# Sheet_1_2026-05-05.net
KiCad netlist of a schematic drawn in Altium Designer
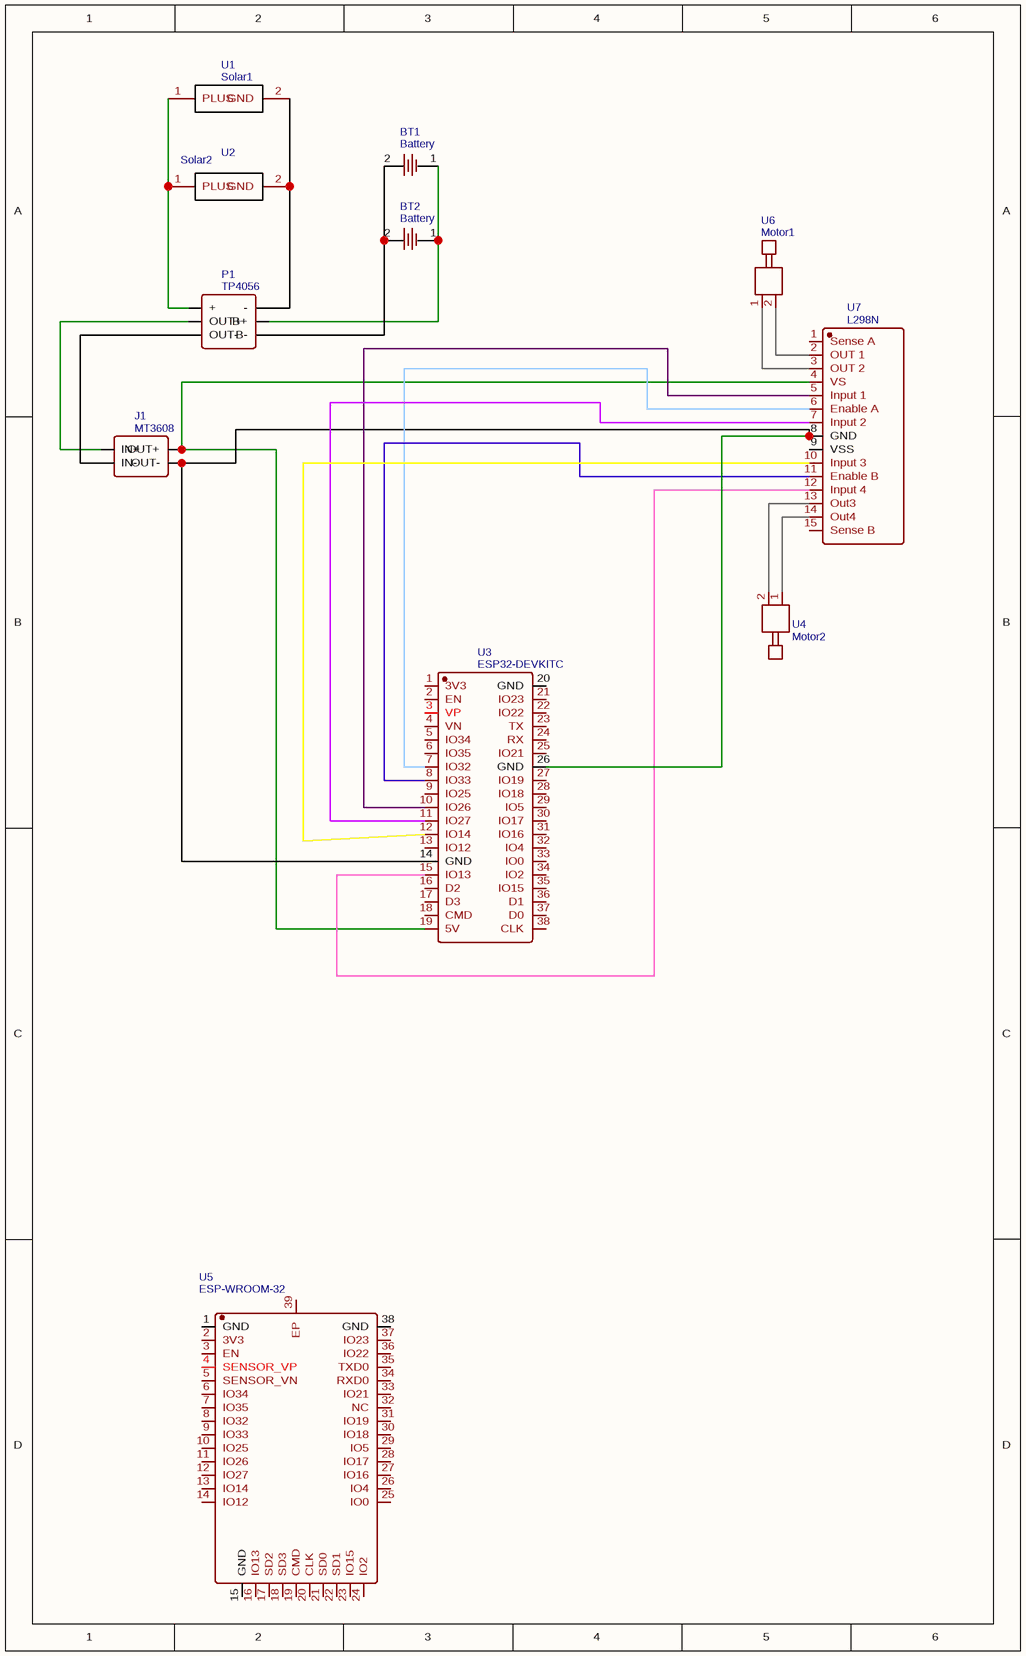
[diagram p0: Sheet_1_2026-05-05.schdoc]

(export (version "E")
  (design (tool "Eeschema 10.0.6"))
  (components
    (comp (ref "BT1")
      (value "Battery")
      (fields
        (field (name "MANUFACTURER") "MYOUNG(美阳)")
        (field (name "MANUFACTURER PART") "BH-18650-B1BA002")
        (field (name "CONTRIBUTOR") "lcsc")
      )
      (libsource (lib "altium-import") (part "root_0_Battery_"))
    )
    (comp (ref "BT2")
      (value "Battery")
      (fields
        (field (name "MANUFACTURER") "MYOUNG(美阳)")
        (field (name "MANUFACTURER PART") "BH-18650-B1BA002")
        (field (name "CONTRIBUTOR") "lcsc")
      )
      (libsource (lib "altium-import") (part "root_0_Battery_"))
    )
    (comp (ref "J1")
      (value "MT3608")
      (fields (field (name "CONTRIBUTOR") "LCEDA_Lib"))
      (libsource (lib "altium-import") (part "root_0_MT3608_"))
    )
    (comp (ref "P1")
      (value "TP4056")
      (fields (field (name "MANUFACTURER") "BOOMELE") (field (name "MANUFACTURER PART") "2X3 2.54mm IDC Box"))
      (libsource (lib "altium-import") (part "root_0_TP4056_"))
    )
    (comp (ref "U1")
      (value "Solar1")
      (fields (field (name "CONTRIBUTOR") "klaslofstedt"))
      (libsource (lib "altium-import") (part "root_0_Solar1_"))
    )
    (comp (ref "U2")
      (value "Solar2")
      (fields (field (name "CONTRIBUTOR") "klaslofstedt"))
      (libsource (lib "altium-import") (part "root_0_Solar2_"))
    )
    (comp (ref "U3")
      (value "ESP32-DEVKITC")
      (fields
        (field (name "MANUFACTURER") "ESPRESSIF(乐鑫)")
        (field (name "MANUFACTURER PART") "ESP32-DevKitC")
        (field (name "CONTRIBUTOR") "lcsc")
      )
      (libsource (lib "altium-import") (part "root_0_ESP32-DEVKITC_"))
    )
    (comp (ref "U4")
      (value "Motor2")
      (fields
        (field (name "MANUFACTURER") "LEADER(立得)")
        (field (name "MANUFACTURER PART") "LCM04084521-B1")
        (field (name "CONTRIBUTOR") "lcsc")
      )
      (libsource (lib "altium-import") (part "root_2_Motor2_"))
    )
    (comp (ref "U5")
      (value "ESP-WROOM-32")
      (fields
        (field (name "MANUFACTURER") "ESPRESSIF(乐鑫)")
        (field (name "MANUFACTURER PART") "ESP32-WROOM-32")
      )
      (libsource (lib "altium-import") (part "root_0_ESP-WROOM-32_"))
    )
    (comp (ref "U6")
      (value "Motor1")
      (fields
        (field (name "MANUFACTURER") "LEADER(立得)")
        (field (name "MANUFACTURER PART") "LCM04084521-B1")
        (field (name "CONTRIBUTOR") "lcsc")
      )
      (libsource (lib "altium-import") (part "root_0_Motor1_"))
    )
    (comp (ref "U7")
      (value "L298N")
      (fields (field (name "MANUFACTURER") "HGSEMI(华冠)") (field (name "CONTRIBUTOR") "LCSC"))
      (libsource (lib "altium-import") (part "root_0_L298N_"))
    )
  )
  (nets
    (net (code "1") (name "Net-(J1-IN+)") (class "Default")
      (node (ref "J1") (pin "1") (pinfunction "IN+_1") (pintype "passive"))
      (node (ref "P1") (pin "3") (pinfunction "OUT+_3") (pintype "passive"))
    )
    (net (code "2") (name "Net-(J1-IN-)") (class "Default")
      (node (ref "J1") (pin "3") (pinfunction "IN-_3") (pintype "passive"))
      (node (ref "P1") (pin "5") (pinfunction "OUT-_5") (pintype "passive"))
    )
    (net (code "3") (name "Net-(J1-OUT+)") (class "Default")
      (node (ref "J1") (pin "2") (pinfunction "OUT+_2") (pintype "passive"))
      (node (ref "U3") (pin "19") (pinfunction "5V_19") (pintype "passive"))
      (node (ref "U7") (pin "4") (pinfunction "VS_4") (pintype "passive"))
    )
    (net (code "4") (name "Net-(J1-OUT-)") (class "Default")
      (node (ref "J1") (pin "4") (pinfunction "OUT-_4") (pintype "passive"))
      (node (ref "U3") (pin "14") (pinfunction "GND_14") (pintype "passive"))
      (node (ref "U3") (pin "26") (pinfunction "GND_26") (pintype "passive"))
      (node (ref "U7") (pin "8") (pinfunction "GND_8") (pintype "passive"))
    )
    (net (code "5") (name "Net-(P1-+)") (class "Default")
      (node (ref "P1") (pin "1") (pinfunction "+_1") (pintype "passive"))
      (node (ref "U1") (pin "1") (pinfunction "PLUS_1") (pintype "passive"))
      (node (ref "U2") (pin "1") (pinfunction "PLUS_1") (pintype "passive"))
    )
    (net (code "6") (name "Net-(P1--)") (class "Default")
      (node (ref "P1") (pin "2") (pinfunction "-_2") (pintype "passive"))
      (node (ref "U1") (pin "2") (pinfunction "GND_2") (pintype "passive"))
      (node (ref "U2") (pin "2") (pinfunction "GND_2") (pintype "passive"))
    )
    (net (code "7") (name "Net-(P1-B+)") (class "Default")
      (node (ref "BT1") (pin "1") (pinfunction "1_1") (pintype "passive"))
      (node (ref "BT2") (pin "1") (pinfunction "1_1") (pintype "passive"))
      (node (ref "P1") (pin "4") (pinfunction "B+_4") (pintype "passive"))
    )
    (net (code "8") (name "Net-(P1-B-)") (class "Default")
      (node (ref "BT1") (pin "2") (pinfunction "2_2") (pintype "passive"))
      (node (ref "BT2") (pin "2") (pinfunction "2_2") (pintype "passive"))
      (node (ref "P1") (pin "6") (pinfunction "B-_6") (pintype "passive"))
    )
    (net (code "9") (name "Net-(U3-IO13)") (class "Default")
      (node (ref "U3") (pin "15") (pinfunction "IO13_15") (pintype "passive"))
      (node (ref "U7") (pin "12") (pinfunction "Input_4_12") (pintype "passive"))
    )
    (net (code "10") (name "Net-(U3-IO14)") (class "Default")
      (node (ref "U3") (pin "12") (pinfunction "IO14_12") (pintype "passive"))
      (node (ref "U7") (pin "10") (pinfunction "Input_3_10") (pintype "passive"))
    )
    (net (code "11") (name "Net-(U3-IO26)") (class "Default")
      (node (ref "U3") (pin "10") (pinfunction "IO26_10") (pintype "passive"))
      (node (ref "U7") (pin "5") (pinfunction "Input_1_5") (pintype "passive"))
    )
    (net (code "12") (name "Net-(U3-IO27)") (class "Default")
      (node (ref "U3") (pin "11") (pinfunction "IO27_11") (pintype "passive"))
      (node (ref "U7") (pin "7") (pinfunction "Input_2_7") (pintype "passive"))
    )
    (net (code "13") (name "Net-(U3-IO32)") (class "Default")
      (node (ref "U3") (pin "7") (pinfunction "IO32_7") (pintype "passive"))
      (node (ref "U7") (pin "6") (pinfunction "Enable_A_6") (pintype "passive"))
    )
    (net (code "14") (name "Net-(U3-IO33)") (class "Default")
      (node (ref "U3") (pin "8") (pinfunction "IO33_8") (pintype "passive"))
      (node (ref "U7") (pin "11") (pinfunction "Enable_B_11") (pintype "passive"))
    )
    (net (code "15") (name "Net-(U7-OUT_1)") (class "Default")
      (node (ref "U6") (pin "2") (pinfunction "2_2") (pintype "passive"))
      (node (ref "U7") (pin "2") (pinfunction "OUT_1_2") (pintype "passive"))
    )
    (net (code "16") (name "Net-(U7-OUT_2)") (class "Default")
      (node (ref "U6") (pin "1") (pinfunction "1_1") (pintype "passive"))
      (node (ref "U7") (pin "3") (pinfunction "OUT_2_3") (pintype "passive"))
    )
    (net (code "17") (name "Net-(U7-Out3)") (class "Default")
      (node (ref "U4") (pin "2") (pinfunction "2_2") (pintype "passive"))
      (node (ref "U7") (pin "13") (pinfunction "Out3_13") (pintype "passive"))
    )
    (net (code "18") (name "Net-(U7-Out4)") (class "Default")
      (node (ref "U4") (pin "1") (pinfunction "1_1") (pintype "passive"))
      (node (ref "U7") (pin "14") (pinfunction "Out4_14") (pintype "passive"))
    )
    (net (code "19") (name "unconnected-(U3-3V3-Pad1)") (class "Default")
      (node (ref "U3") (pin "1") (pinfunction "3V3_1") (pintype "passive"))
    )
    (net (code "20") (name "unconnected-(U3-CLK-Pad38)") (class "Default")
      (node (ref "U3") (pin "38") (pinfunction "CLK_38") (pintype "passive"))
    )
    (net (code "21") (name "unconnected-(U3-CMD-Pad18)") (class "Default")
      (node (ref "U3") (pin "18") (pinfunction "CMD_18") (pintype "passive"))
    )
    (net (code "22") (name "unconnected-(U3-D0-Pad37)") (class "Default")
      (node (ref "U3") (pin "37") (pinfunction "D0_37") (pintype "passive"))
    )
    (net (code "23") (name "unconnected-(U3-D1-Pad36)") (class "Default")
      (node (ref "U3") (pin "36") (pinfunction "D1_36") (pintype "passive"))
    )
    (net (code "24") (name "unconnected-(U3-D2-Pad16)") (class "Default")
      (node (ref "U3") (pin "16") (pinfunction "D2_16") (pintype "passive"))
    )
    (net (code "25") (name "unconnected-(U3-D3-Pad17)") (class "Default")
      (node (ref "U3") (pin "17") (pinfunction "D3_17") (pintype "passive"))
    )
    (net (code "26") (name "unconnected-(U3-EN-Pad2)") (class "Default")
      (node (ref "U3") (pin "2") (pinfunction "EN_2") (pintype "passive"))
    )
    (net (code "27") (name "unconnected-(U3-GND-Pad20)") (class "Default")
      (node (ref "U3") (pin "20") (pinfunction "GND_20") (pintype "passive"))
    )
    (net (code "28") (name "unconnected-(U3-IO0-Pad33)") (class "Default")
      (node (ref "U3") (pin "33") (pinfunction "IO0_33") (pintype "passive"))
    )
    (net (code "29") (name "unconnected-(U3-IO2-Pad34)") (class "Default")
      (node (ref "U3") (pin "34") (pinfunction "IO2_34") (pintype "passive"))
    )
    (net (code "30") (name "unconnected-(U3-IO4-Pad32)") (class "Default")
      (node (ref "U3") (pin "32") (pinfunction "IO4_32") (pintype "passive"))
    )
    (net (code "31") (name "unconnected-(U3-IO5-Pad29)") (class "Default")
      (node (ref "U3") (pin "29") (pinfunction "IO5_29") (pintype "passive"))
    )
    (net (code "32") (name "unconnected-(U3-IO12-Pad13)") (class "Default")
      (node (ref "U3") (pin "13") (pinfunction "IO12_13") (pintype "passive"))
    )
    (net (code "33") (name "unconnected-(U3-IO15-Pad35)") (class "Default")
      (node (ref "U3") (pin "35") (pinfunction "IO15_35") (pintype "passive"))
    )
    (net (code "34") (name "unconnected-(U3-IO16-Pad31)") (class "Default")
      (node (ref "U3") (pin "31") (pinfunction "IO16_31") (pintype "passive"))
    )
    (net (code "35") (name "unconnected-(U3-IO17-Pad30)") (class "Default")
      (node (ref "U3") (pin "30") (pinfunction "IO17_30") (pintype "passive"))
    )
    (net (code "36") (name "unconnected-(U3-IO18-Pad28)") (class "Default")
      (node (ref "U3") (pin "28") (pinfunction "IO18_28") (pintype "passive"))
    )
    (net (code "37") (name "unconnected-(U3-IO19-Pad27)") (class "Default")
      (node (ref "U3") (pin "27") (pinfunction "IO19_27") (pintype "passive"))
    )
    (net (code "38") (name "unconnected-(U3-IO21-Pad25)") (class "Default")
      (node (ref "U3") (pin "25") (pinfunction "IO21_25") (pintype "passive"))
    )
    (net (code "39") (name "unconnected-(U3-IO22-Pad22)") (class "Default")
      (node (ref "U3") (pin "22") (pinfunction "IO22_22") (pintype "passive"))
    )
    (net (code "40") (name "unconnected-(U3-IO23-Pad21)") (class "Default")
      (node (ref "U3") (pin "21") (pinfunction "IO23_21") (pintype "passive"))
    )
    (net (code "41") (name "unconnected-(U3-IO25-Pad9)") (class "Default")
      (node (ref "U3") (pin "9") (pinfunction "IO25_9") (pintype "passive"))
    )
    (net (code "42") (name "unconnected-(U3-IO34-Pad5)") (class "Default")
      (node (ref "U3") (pin "5") (pinfunction "IO34_5") (pintype "passive"))
    )
    (net (code "43") (name "unconnected-(U3-IO35-Pad6)") (class "Default")
      (node (ref "U3") (pin "6") (pinfunction "IO35_6") (pintype "passive"))
    )
    (net (code "44") (name "unconnected-(U3-RX-Pad24)") (class "Default")
      (node (ref "U3") (pin "24") (pinfunction "RX_24") (pintype "passive"))
    )
    (net (code "45") (name "unconnected-(U3-TX-Pad23)") (class "Default")
      (node (ref "U3") (pin "23") (pinfunction "TX_23") (pintype "passive"))
    )
    (net (code "46") (name "unconnected-(U3-VN-Pad4)") (class "Default")
      (node (ref "U3") (pin "4") (pinfunction "VN_4") (pintype "passive"))
    )
    (net (code "47") (name "unconnected-(U3-VP-Pad3)") (class "Default")
      (node (ref "U3") (pin "3") (pinfunction "VP_3") (pintype "passive"))
    )
    (net (code "48") (name "unconnected-(U5-3V3-Pad2)") (class "Default")
      (node (ref "U5") (pin "2") (pinfunction "3V3_2") (pintype "passive"))
    )
    (net (code "49") (name "unconnected-(U5-CLK-Pad20)") (class "Default")
      (node (ref "U5") (pin "20") (pinfunction "CLK_20") (pintype "passive"))
    )
    (net (code "50") (name "unconnected-(U5-CMD-Pad19)") (class "Default")
      (node (ref "U5") (pin "19") (pinfunction "CMD_19") (pintype "passive"))
    )
    (net (code "51") (name "unconnected-(U5-EN-Pad3)") (class "Default")
      (node (ref "U5") (pin "3") (pinfunction "EN_3") (pintype "passive"))
    )
    (net (code "52") (name "unconnected-(U5-EP-Pad39)") (class "Default")
      (node (ref "U5") (pin "39") (pinfunction "EP_39") (pintype "passive"))
    )
    (net (code "53") (name "unconnected-(U5-GND-Pad1)") (class "Default")
      (node (ref "U5") (pin "1") (pinfunction "GND_1") (pintype "passive"))
    )
    (net (code "54") (name "unconnected-(U5-GND-Pad15)") (class "Default")
      (node (ref "U5") (pin "15") (pinfunction "GND_15") (pintype "passive"))
    )
    (net (code "55") (name "unconnected-(U5-GND-Pad38)") (class "Default")
      (node (ref "U5") (pin "38") (pinfunction "GND_38") (pintype "passive"))
    )
    (net (code "56") (name "unconnected-(U5-IO0-Pad25)") (class "Default")
      (node (ref "U5") (pin "25") (pinfunction "IO0_25") (pintype "passive"))
    )
    (net (code "57") (name "unconnected-(U5-IO2-Pad24)") (class "Default")
      (node (ref "U5") (pin "24") (pinfunction "IO2_24") (pintype "passive"))
    )
    (net (code "58") (name "unconnected-(U5-IO4-Pad26)") (class "Default")
      (node (ref "U5") (pin "26") (pinfunction "IO4_26") (pintype "passive"))
    )
    (net (code "59") (name "unconnected-(U5-IO5-Pad29)") (class "Default")
      (node (ref "U5") (pin "29") (pinfunction "IO5_29") (pintype "passive"))
    )
    (net (code "60") (name "unconnected-(U5-IO12-Pad14)") (class "Default")
      (node (ref "U5") (pin "14") (pinfunction "IO12_14") (pintype "passive"))
    )
    (net (code "61") (name "unconnected-(U5-IO13-Pad16)") (class "Default")
      (node (ref "U5") (pin "16") (pinfunction "IO13_16") (pintype "passive"))
    )
    (net (code "62") (name "unconnected-(U5-IO14-Pad13)") (class "Default")
      (node (ref "U5") (pin "13") (pinfunction "IO14_13") (pintype "passive"))
    )
    (net (code "63") (name "unconnected-(U5-IO15-Pad23)") (class "Default")
      (node (ref "U5") (pin "23") (pinfunction "IO15_23") (pintype "passive"))
    )
    (net (code "64") (name "unconnected-(U5-IO16-Pad27)") (class "Default")
      (node (ref "U5") (pin "27") (pinfunction "IO16_27") (pintype "passive"))
    )
    (net (code "65") (name "unconnected-(U5-IO17-Pad28)") (class "Default")
      (node (ref "U5") (pin "28") (pinfunction "IO17_28") (pintype "passive"))
    )
    (net (code "66") (name "unconnected-(U5-IO18-Pad30)") (class "Default")
      (node (ref "U5") (pin "30") (pinfunction "IO18_30") (pintype "passive"))
    )
    (net (code "67") (name "unconnected-(U5-IO19-Pad31)") (class "Default")
      (node (ref "U5") (pin "31") (pinfunction "IO19_31") (pintype "passive"))
    )
    (net (code "68") (name "unconnected-(U5-IO21-Pad33)") (class "Default")
      (node (ref "U5") (pin "33") (pinfunction "IO21_33") (pintype "passive"))
    )
    (net (code "69") (name "unconnected-(U5-IO22-Pad36)") (class "Default")
      (node (ref "U5") (pin "36") (pinfunction "IO22_36") (pintype "passive"))
    )
    (net (code "70") (name "unconnected-(U5-IO23-Pad37)") (class "Default")
      (node (ref "U5") (pin "37") (pinfunction "IO23_37") (pintype "passive"))
    )
    (net (code "71") (name "unconnected-(U5-IO25-Pad10)") (class "Default")
      (node (ref "U5") (pin "10") (pinfunction "IO25_10") (pintype "passive"))
    )
    (net (code "72") (name "unconnected-(U5-IO26-Pad11)") (class "Default")
      (node (ref "U5") (pin "11") (pinfunction "IO26_11") (pintype "passive"))
    )
    (net (code "73") (name "unconnected-(U5-IO27-Pad12)") (class "Default")
      (node (ref "U5") (pin "12") (pinfunction "IO27_12") (pintype "passive"))
    )
    (net (code "74") (name "unconnected-(U5-IO32-Pad8)") (class "Default")
      (node (ref "U5") (pin "8") (pinfunction "IO32_8") (pintype "passive"))
    )
    (net (code "75") (name "unconnected-(U5-IO33-Pad9)") (class "Default")
      (node (ref "U5") (pin "9") (pinfunction "IO33_9") (pintype "passive"))
    )
    (net (code "76") (name "unconnected-(U5-IO34-Pad6)") (class "Default")
      (node (ref "U5") (pin "6") (pinfunction "IO34_6") (pintype "passive"))
    )
    (net (code "77") (name "unconnected-(U5-IO35-Pad7)") (class "Default")
      (node (ref "U5") (pin "7") (pinfunction "IO35_7") (pintype "passive"))
    )
    (net (code "78") (name "unconnected-(U5-NC-Pad32)") (class "Default")
      (node (ref "U5") (pin "32") (pinfunction "NC_32") (pintype "passive"))
    )
    (net (code "79") (name "unconnected-(U5-RXD0-Pad34)") (class "Default")
      (node (ref "U5") (pin "34") (pinfunction "RXD0_34") (pintype "passive"))
    )
    (net (code "80") (name "unconnected-(U5-SD0-Pad21)") (class "Default")
      (node (ref "U5") (pin "21") (pinfunction "SD0_21") (pintype "passive"))
    )
    (net (code "81") (name "unconnected-(U5-SD1-Pad22)") (class "Default")
      (node (ref "U5") (pin "22") (pinfunction "SD1_22") (pintype "passive"))
    )
    (net (code "82") (name "unconnected-(U5-SD2-Pad17)") (class "Default")
      (node (ref "U5") (pin "17") (pinfunction "SD2_17") (pintype "passive"))
    )
    (net (code "83") (name "unconnected-(U5-SD3-Pad18)") (class "Default")
      (node (ref "U5") (pin "18") (pinfunction "SD3_18") (pintype "passive"))
    )
    (net (code "84") (name "unconnected-(U5-SENSOR_VN-Pad5)") (class "Default")
      (node (ref "U5") (pin "5") (pinfunction "SENSOR_VN_5") (pintype "passive"))
    )
    (net (code "85") (name "unconnected-(U5-SENSOR_VP-Pad4)") (class "Default")
      (node (ref "U5") (pin "4") (pinfunction "SENSOR_VP_4") (pintype "passive"))
    )
    (net (code "86") (name "unconnected-(U5-TXD0-Pad35)") (class "Default")
      (node (ref "U5") (pin "35") (pinfunction "TXD0_35") (pintype "passive"))
    )
    (net (code "87") (name "unconnected-(U7-Sense_A-Pad1)") (class "Default")
      (node (ref "U7") (pin "1") (pinfunction "Sense_A_1") (pintype "passive"))
    )
    (net (code "88") (name "unconnected-(U7-Sense_B-Pad15)") (class "Default")
      (node (ref "U7") (pin "15") (pinfunction "Sense_B_15") (pintype "passive"))
    )
    (net (code "89") (name "unconnected-(U7-VSS-Pad9)") (class "Default")
      (node (ref "U7") (pin "9") (pinfunction "VSS_9") (pintype "passive"))
    )
  )
)
